# ddrive-esp-deadrail-1-6.net
KiCad netlist of a schematic drawn in EAGLE
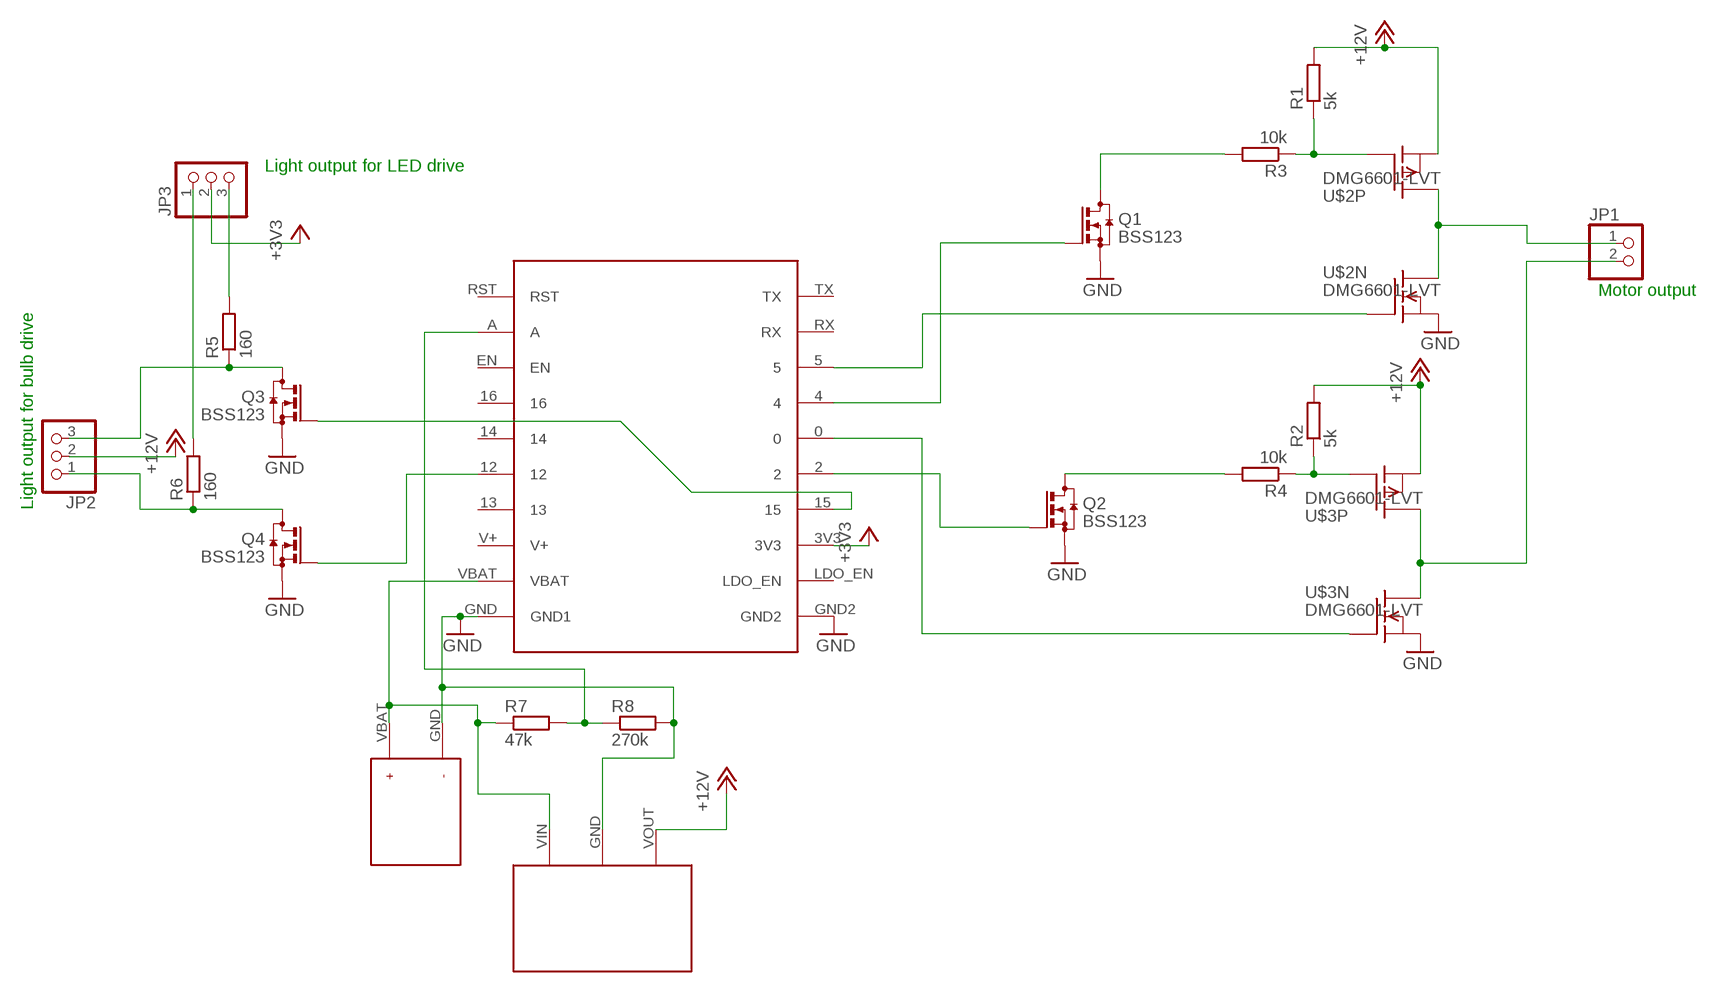
[diagram p0: schematic, sheet 1]

(export (version "E")
  (design (tool "Eeschema 10.0.6"))
  (components
    (comp (ref "JP1")
      (value "PINHD-1X2")
      (footprint "eagle-import:1X02")
      (libsource (lib "eagle-import") (part "PINHD-1X2"))
    )
    (comp (ref "JP2")
      (value "PINHD-1X3")
      (footprint "eagle-import:1X03")
      (libsource (lib "eagle-import") (part "PINHD-1X3"))
    )
    (comp (ref "JP3")
      (value "PINHD-1X3")
      (footprint "eagle-import:1X03")
      (libsource (lib "eagle-import") (part "PINHD-1X3"))
    )
    (comp (ref "Q1")
      (value "BSS123")
      (footprint "eagle-import:SOT23")
      (libsource (lib "eagle-import") (part "BSS123"))
    )
    (comp (ref "Q2")
      (value "BSS123")
      (footprint "eagle-import:SOT23")
      (libsource (lib "eagle-import") (part "BSS123"))
    )
    (comp (ref "Q3")
      (value "BSS123")
      (footprint "eagle-import:SOT23")
      (libsource (lib "eagle-import") (part "BSS123"))
    )
    (comp (ref "Q4")
      (value "BSS123")
      (footprint "eagle-import:SOT23")
      (libsource (lib "eagle-import") (part "BSS123"))
    )
    (comp (ref "R1")
      (value "5k")
      (footprint "eagle-import:R0805")
      (libsource (lib "eagle-import") (part "R-EU_R0805"))
    )
    (comp (ref "R2")
      (value "5k")
      (footprint "eagle-import:R0805")
      (libsource (lib "eagle-import") (part "R-EU_R0805"))
    )
    (comp (ref "R3")
      (value "10k")
      (footprint "eagle-import:R0805")
      (libsource (lib "eagle-import") (part "R-EU_R0805"))
    )
    (comp (ref "R4")
      (value "10k")
      (footprint "eagle-import:R0805")
      (libsource (lib "eagle-import") (part "R-EU_R0805"))
    )
    (comp (ref "R5")
      (value "160")
      (footprint "eagle-import:R0805")
      (libsource (lib "eagle-import") (part "R-EU_R0805"))
    )
    (comp (ref "R6")
      (value "160")
      (footprint "eagle-import:R0805")
      (libsource (lib "eagle-import") (part "R-EU_R0805"))
    )
    (comp (ref "R7")
      (value "47k")
      (footprint "eagle-import:R0805")
      (libsource (lib "eagle-import") (part "R-EU_R0805"))
    )
    (comp (ref "R8")
      (value "270k")
      (footprint "eagle-import:R0805")
      (libsource (lib "eagle-import") (part "R-EU_R0805"))
    )
    (comp (ref "U$1")
      (value "ESP12-HUZZAH")
      (footprint "eagle-import:ESP12-HUZZAH")
      (libsource (lib "eagle-import") (part "ESP12-HUZZAH"))
    )
    (comp (ref "U$2")
      (value "DMG6601-LVT")
      (footprint "eagle-import:TSOT-26")
      (libsource (lib "eagle-import") (part "DMG6601-LVT"))
    )
    (comp (ref "U$3")
      (value "DMG6601-LVT")
      (footprint "eagle-import:TSOT-26")
      (libsource (lib "eagle-import") (part "DMG6601-LVT"))
    )
    (comp (ref "U$4")
      (value "JST-PINHD")
      (footprint "eagle-import:JST-PINHDR")
      (libsource (lib "eagle-import") (part "JST-PINHD"))
    )
    (comp (ref "U$5")
      (value "POLOLU-VREG12")
      (footprint "eagle-import:POLOLU-REGULATOR")
      (libsource (lib "eagle-import") (part "POLOLU-VREG12"))
    )
  )
  (nets
    (net (code "1") (name "+3V3") (class "Default")
      (node (ref "JP3") (pin "2") (pinfunction "2_2") (pintype "passive"))
      (node (ref "U$1") (pin "3V3") (pinfunction "3V3_3V3") (pintype "power_in"))
    )
    (net (code "2") (name "+12V") (class "Default")
      (node (ref "JP2") (pin "2") (pinfunction "2_2") (pintype "passive"))
      (node (ref "R1") (pin "2") (pinfunction "2_2") (pintype "passive"))
      (node (ref "R2") (pin "2") (pinfunction "2_2") (pintype "passive"))
      (node (ref "U$2") (pin "2") (pinfunction "S_2") (pintype "passive"))
      (node (ref "U$3") (pin "2") (pinfunction "S_2") (pintype "passive"))
      (node (ref "U$5") (pin "VOUT") (pinfunction "VOUT_VOUT") (pintype "bidirectional"))
    )
    (net (code "3") (name "/V+") (class "Default")
      (node (ref "U$1") (pin "V+") (pinfunction "V+_V+") (pintype "power_in"))
    )
    (net (code "4") (name "GND") (class "Default")
      (node (ref "Q1") (pin "2") (pinfunction "S_2") (pintype "passive"))
      (node (ref "Q2") (pin "2") (pinfunction "S_2") (pintype "passive"))
      (node (ref "Q3") (pin "2") (pinfunction "S_2") (pintype "passive"))
      (node (ref "Q4") (pin "2") (pinfunction "S_2") (pintype "passive"))
      (node (ref "R8") (pin "2") (pinfunction "2_2") (pintype "passive"))
      (node (ref "U$1") (pin "GND") (pinfunction "GND1_GND") (pintype "power_in"))
      (node (ref "U$1") (pin "GND2") (pinfunction "GND2_GND2") (pintype "power_in"))
      (node (ref "U$2") (pin "5") (pinfunction "S_5") (pintype "passive"))
      (node (ref "U$3") (pin "5") (pinfunction "S_5") (pintype "passive"))
      (node (ref "U$4") (pin "GND") (pinfunction "P$1_GND") (pintype "power_in"))
      (node (ref "U$5") (pin "GND") (pinfunction "GND_GND") (pintype "bidirectional"))
    )
    (net (code "5") (name "Net-(JP3-Pad1)") (class "Default")
      (node (ref "JP3") (pin "1") (pinfunction "1_1") (pintype "passive"))
      (node (ref "R6") (pin "2") (pinfunction "2_2") (pintype "passive"))
    )
    (net (code "6") (name "Net-(JP3-Pad3)") (class "Default")
      (node (ref "JP3") (pin "3") (pinfunction "3_3") (pintype "passive"))
      (node (ref "R5") (pin "2") (pinfunction "2_2") (pintype "passive"))
    )
    (net (code "7") (name "Net-(Q1-D)") (class "Default")
      (node (ref "Q1") (pin "3") (pinfunction "D_3") (pintype "passive"))
      (node (ref "R3") (pin "2") (pinfunction "2_2") (pintype "passive"))
    )
    (net (code "8") (name "Net-(Q1-G)") (class "Default")
      (node (ref "Q1") (pin "1") (pinfunction "G_1") (pintype "passive"))
      (node (ref "U$1") (pin "4") (pinfunction "4_4") (pintype "bidirectional"))
    )
    (net (code "9") (name "Net-(Q2-D)") (class "Default")
      (node (ref "Q2") (pin "3") (pinfunction "D_3") (pintype "passive"))
      (node (ref "R4") (pin "2") (pinfunction "2_2") (pintype "passive"))
    )
    (net (code "10") (name "Net-(Q2-G)") (class "Default")
      (node (ref "Q2") (pin "1") (pinfunction "G_1") (pintype "passive"))
      (node (ref "U$1") (pin "2") (pinfunction "2_2") (pintype "bidirectional"))
    )
    (net (code "11") (name "Net-(Q3-D)") (class "Default")
      (node (ref "JP2") (pin "3") (pinfunction "3_3") (pintype "passive"))
      (node (ref "Q3") (pin "3") (pinfunction "D_3") (pintype "passive"))
      (node (ref "R5") (pin "1") (pinfunction "1_1") (pintype "passive"))
    )
    (net (code "12") (name "Net-(Q3-G)") (class "Default")
      (node (ref "Q3") (pin "1") (pinfunction "G_1") (pintype "passive"))
      (node (ref "U$1") (pin "15") (pinfunction "15_15") (pintype "bidirectional"))
    )
    (net (code "13") (name "Net-(Q4-D)") (class "Default")
      (node (ref "JP2") (pin "1") (pinfunction "1_1") (pintype "passive"))
      (node (ref "Q4") (pin "3") (pinfunction "D_3") (pintype "passive"))
      (node (ref "R6") (pin "1") (pinfunction "1_1") (pintype "passive"))
    )
    (net (code "14") (name "Net-(Q4-G)") (class "Default")
      (node (ref "Q4") (pin "1") (pinfunction "G_1") (pintype "passive"))
      (node (ref "U$1") (pin "12") (pinfunction "12_12") (pintype "bidirectional"))
    )
    (net (code "15") (name "Net-(R7-Pad2)") (class "Default")
      (node (ref "R7") (pin "2") (pinfunction "2_2") (pintype "passive"))
      (node (ref "R8") (pin "1") (pinfunction "1_1") (pintype "passive"))
      (node (ref "U$1") (pin "A") (pinfunction "A_A") (pintype "bidirectional"))
    )
    (net (code "16") (name "Net-(U$2A-D)") (class "Default")
      (node (ref "JP1") (pin "1") (pinfunction "1_1") (pintype "passive"))
      (node (ref "U$2") (pin "4") (pinfunction "D_4") (pintype "passive"))
      (node (ref "U$2") (pin "6") (pinfunction "D_6") (pintype "passive"))
    )
    (net (code "17") (name "Net-(U$2A-G)") (class "Default")
      (node (ref "U$1") (pin "5") (pinfunction "5_5") (pintype "bidirectional"))
      (node (ref "U$2") (pin "1") (pinfunction "G_1") (pintype "passive"))
    )
    (net (code "18") (name "Net-(U$2B-G)") (class "Default")
      (node (ref "R1") (pin "1") (pinfunction "1_1") (pintype "passive"))
      (node (ref "R3") (pin "1") (pinfunction "1_1") (pintype "passive"))
      (node (ref "U$2") (pin "3") (pinfunction "G_3") (pintype "passive"))
    )
    (net (code "19") (name "Net-(U$3A-D)") (class "Default")
      (node (ref "JP1") (pin "2") (pinfunction "2_2") (pintype "passive"))
      (node (ref "U$3") (pin "4") (pinfunction "D_4") (pintype "passive"))
      (node (ref "U$3") (pin "6") (pinfunction "D_6") (pintype "passive"))
    )
    (net (code "20") (name "Net-(U$3A-G)") (class "Default")
      (node (ref "U$1") (pin "0") (pinfunction "0_0") (pintype "bidirectional"))
      (node (ref "U$3") (pin "1") (pinfunction "G_1") (pintype "passive"))
    )
    (net (code "21") (name "Net-(U$3B-G)") (class "Default")
      (node (ref "R2") (pin "1") (pinfunction "1_1") (pintype "passive"))
      (node (ref "R4") (pin "1") (pinfunction "1_1") (pintype "passive"))
      (node (ref "U$3") (pin "3") (pinfunction "G_3") (pintype "passive"))
    )
    (net (code "22") (name "Net-(U$4-P$2)") (class "Default")
      (node (ref "R7") (pin "1") (pinfunction "1_1") (pintype "passive"))
      (node (ref "U$1") (pin "VBAT") (pinfunction "VBAT_VBAT") (pintype "power_in"))
      (node (ref "U$4") (pin "VBAT") (pinfunction "P$2_VBAT") (pintype "power_in"))
      (node (ref "U$5") (pin "VIN") (pinfunction "VIN_VIN") (pintype "bidirectional"))
    )
    (net (code "23") (name "unconnected-(U$1-Pad13)") (class "Default")
      (node (ref "U$1") (pin "13") (pinfunction "13_13") (pintype "bidirectional"))
    )
    (net (code "24") (name "unconnected-(U$1-Pad14)") (class "Default")
      (node (ref "U$1") (pin "14") (pinfunction "14_14") (pintype "bidirectional"))
    )
    (net (code "25") (name "unconnected-(U$1-Pad16)") (class "Default")
      (node (ref "U$1") (pin "16") (pinfunction "16_16") (pintype "bidirectional"))
    )
    (net (code "26") (name "unconnected-(U$1-PadEN)") (class "Default")
      (node (ref "U$1") (pin "EN") (pinfunction "EN_EN") (pintype "bidirectional"))
    )
    (net (code "27") (name "unconnected-(U$1-PadLDO_EN)") (class "Default")
      (node (ref "U$1") (pin "LDO_EN") (pinfunction "LDO_EN_LDO_EN") (pintype "bidirectional"))
    )
    (net (code "28") (name "unconnected-(U$1-PadRST)") (class "Default")
      (node (ref "U$1") (pin "RST") (pinfunction "RST_RST") (pintype "bidirectional"))
    )
    (net (code "29") (name "unconnected-(U$1-PadRX)") (class "Default")
      (node (ref "U$1") (pin "RX") (pinfunction "RX_RX") (pintype "bidirectional"))
    )
    (net (code "30") (name "unconnected-(U$1-PadTX)") (class "Default")
      (node (ref "U$1") (pin "TX") (pinfunction "TX_TX") (pintype "bidirectional"))
    )
  )
)
